# trigger_interface.net
KiCad netlist of a schematic drawn in Altium Designer
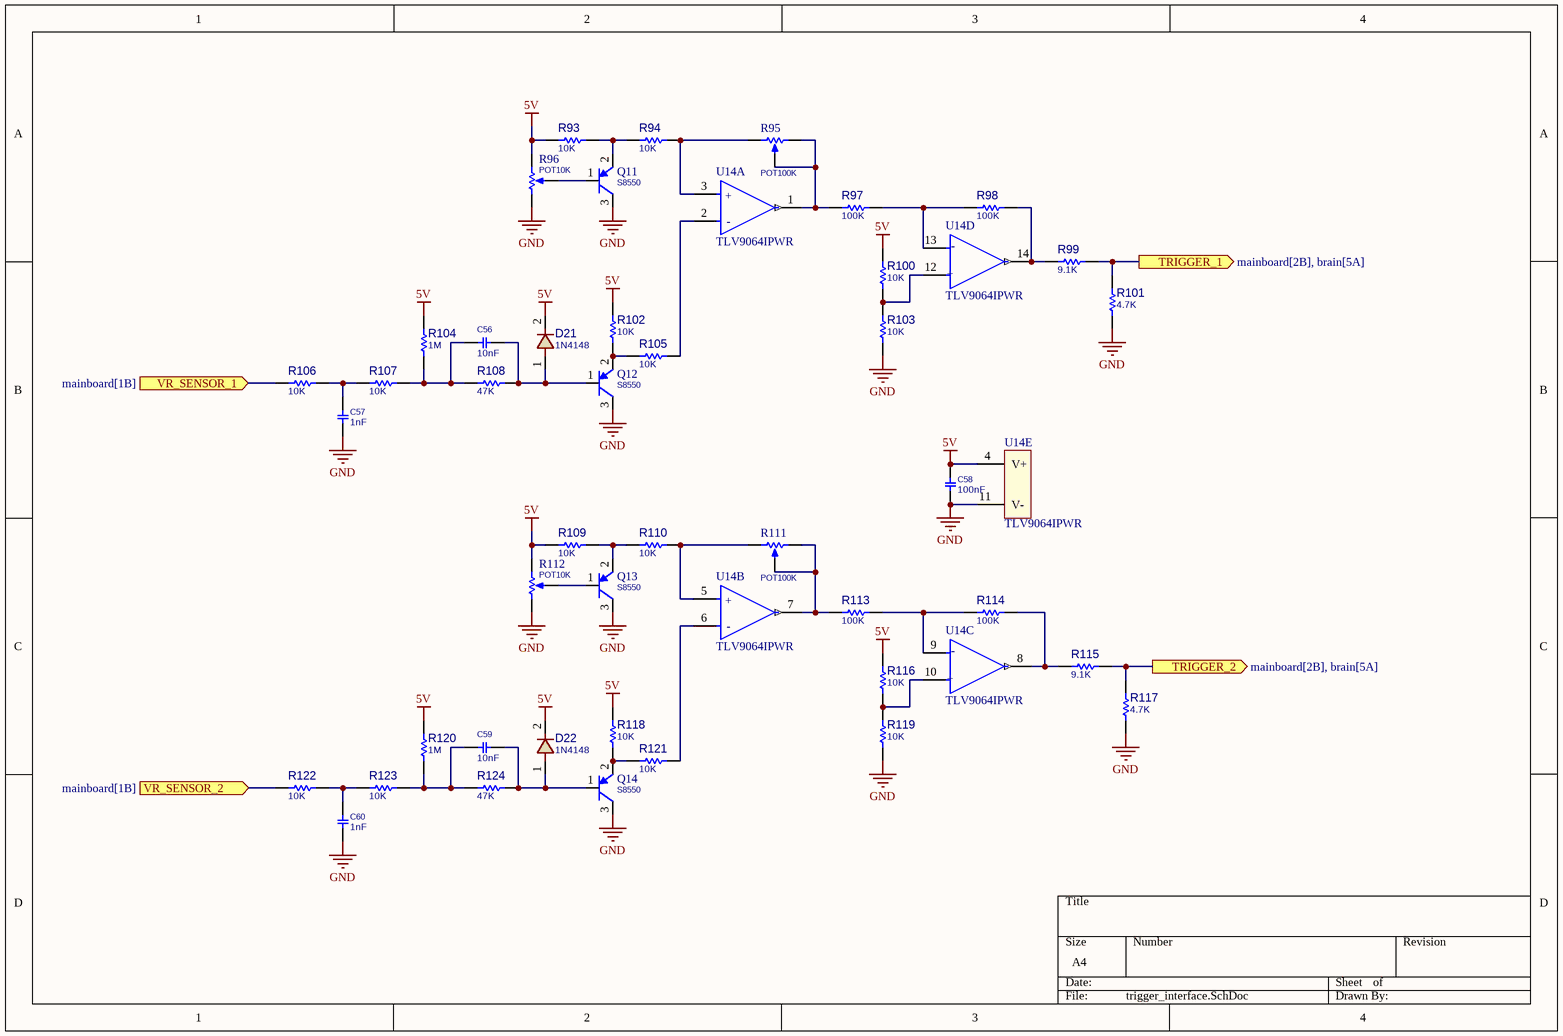
[diagram p0: trigger_interface.SchDoc]

(export (version "E")
  (design (tool "Eeschema 10.0.6"))
  (components
    (comp (ref "C56")
      (value "10nF")
      (footprint "C0805")
      (description "CAP, MLCC")
      (fields (field (name "MANF_P#") "MANF_PART#") (field (name "MANF") "Murata"))
      (libsource (lib "passive_smd") (part "CAP_SMD_MLCC"))
    )
    (comp (ref "C57")
      (value "1nF")
      (footprint "C0805")
      (description "CAP, MLCC")
      (fields (field (name "MANF_P#") "MANF_PART#") (field (name "MANF") "Murata"))
      (libsource (lib "passive_smd") (part "CAP_SMD_MLCC"))
    )
    (comp (ref "C58")
      (value "100nF")
      (footprint "C0805")
      (description "CAP, MLCC")
      (fields (field (name "MANF_P#") "MANF_PART#") (field (name "MANF") "Murata"))
      (libsource (lib "passive_smd") (part "CAP_SMD_MLCC"))
    )
    (comp (ref "C59")
      (value "10nF")
      (footprint "C0805")
      (description "CAP, MLCC")
      (fields (field (name "MANF_P#") "MANF_PART#") (field (name "MANF") "Murata"))
      (libsource (lib "passive_smd") (part "CAP_SMD_MLCC"))
    )
    (comp (ref "C60")
      (value "1nF")
      (footprint "C0805")
      (description "CAP, MLCC")
      (fields (field (name "MANF_P#") "MANF_PART#") (field (name "MANF") "Murata"))
      (libsource (lib "passive_smd") (part "CAP_SMD_MLCC"))
    )
    (comp (ref "D21")
      (value "1N4148")
      (footprint "D_SOD80")
      (description "DIODE, FAST SWTICHING, 0.3A, 0.5W")
      (fields (field (name "MANF") "MANF"))
      (libsource (lib "diode") (part "DIODE_SMD_1N4148_SOD80"))
    )
    (comp (ref "D22")
      (value "1N4148")
      (footprint "D_SOD80")
      (description "DIODE, FAST SWTICHING, 0.3A, 0.5W")
      (fields (field (name "MANF") "MANF"))
      (libsource (lib "diode") (part "DIODE_SMD_1N4148_SOD80"))
    )
    (comp (ref "Q11")
      (value "S8550")
      (footprint "SOT23_3")
      (description "BJT, PNP, 25v, 0.5A, SMD, SOT23")
      (libsource (lib "transistor_bjt") (part "PNP_S8550_SOT23"))
    )
    (comp (ref "Q12")
      (value "S8550")
      (footprint "SOT23_3")
      (description "BJT, PNP, 25v, 0.5A, SMD, SOT23")
      (libsource (lib "transistor_bjt") (part "PNP_S8550_SOT23"))
    )
    (comp (ref "Q13")
      (value "S8550")
      (footprint "SOT23_3")
      (description "BJT, PNP, 25v, 0.5A, SMD, SOT23")
      (libsource (lib "transistor_bjt") (part "PNP_S8550_SOT23"))
    )
    (comp (ref "Q14")
      (value "S8550")
      (footprint "SOT23_3")
      (description "BJT, PNP, 25v, 0.5A, SMD, SOT23")
      (libsource (lib "transistor_bjt") (part "PNP_S8550_SOT23"))
    )
    (comp (ref "R93")
      (value "10K")
      (footprint "R0805")
      (description "RESISTOR, SMD")
      (libsource (lib "passive_smd") (part "RES_SMD"))
    )
    (comp (ref "R94")
      (value "10K")
      (footprint "R0805")
      (description "RESISTOR, SMD")
      (libsource (lib "passive_smd") (part "RES_SMD"))
    )
    (comp (ref "R95")
      (value "POT100K")
      (footprint "POT_7X5")
      (description "RESISTOR, THD, Potentiometer")
      (libsource (lib "resistor_pot_trimmer") (part "RES_THD_POT_7X5"))
    )
    (comp (ref "R96")
      (value "POT10K")
      (footprint "POT_7X5")
      (description "RESISTOR, THD, Potentiometer")
      (libsource (lib "resistor_pot_trimmer") (part "RES_THD_POT_7X5"))
    )
    (comp (ref "R97")
      (value "100K")
      (footprint "R0805")
      (description "RESISTOR, SMD")
      (libsource (lib "passive_smd") (part "RES_SMD"))
    )
    (comp (ref "R98")
      (value "100K")
      (footprint "R0805")
      (description "RESISTOR, SMD")
      (libsource (lib "passive_smd") (part "RES_SMD"))
    )
    (comp (ref "R99")
      (value "9.1K")
      (footprint "R0805")
      (description "RESISTOR, SMD")
      (libsource (lib "passive_smd") (part "RES_SMD"))
    )
    (comp (ref "R100")
      (value "10K")
      (footprint "R0805")
      (description "RESISTOR, SMD")
      (libsource (lib "passive_smd") (part "RES_SMD"))
    )
    (comp (ref "R101")
      (value "4.7K")
      (footprint "R0805")
      (description "RESISTOR, SMD")
      (libsource (lib "passive_smd") (part "RES_SMD"))
    )
    (comp (ref "R102")
      (value "10K")
      (footprint "R0805")
      (description "RESISTOR, SMD")
      (libsource (lib "passive_smd") (part "RES_SMD"))
    )
    (comp (ref "R103")
      (value "10K")
      (footprint "R0805")
      (description "RESISTOR, SMD")
      (libsource (lib "passive_smd") (part "RES_SMD"))
    )
    (comp (ref "R104")
      (value "1M")
      (footprint "R0805")
      (description "RESISTOR, SMD")
      (libsource (lib "passive_smd") (part "RES_SMD"))
    )
    (comp (ref "R105")
      (value "10K")
      (footprint "R0805")
      (description "RESISTOR, SMD")
      (libsource (lib "passive_smd") (part "RES_SMD"))
    )
    (comp (ref "R106")
      (value "10K")
      (footprint "R0805")
      (description "RESISTOR, SMD")
      (libsource (lib "passive_smd") (part "RES_SMD"))
    )
    (comp (ref "R107")
      (value "10K")
      (footprint "R0805")
      (description "RESISTOR, SMD")
      (libsource (lib "passive_smd") (part "RES_SMD"))
    )
    (comp (ref "R108")
      (value "47K")
      (footprint "R0805")
      (description "RESISTOR, SMD")
      (libsource (lib "passive_smd") (part "RES_SMD"))
    )
    (comp (ref "R109")
      (value "10K")
      (footprint "R0805")
      (description "RESISTOR, SMD")
      (libsource (lib "passive_smd") (part "RES_SMD"))
    )
    (comp (ref "R110")
      (value "10K")
      (footprint "R0805")
      (description "RESISTOR, SMD")
      (libsource (lib "passive_smd") (part "RES_SMD"))
    )
    (comp (ref "R111")
      (value "POT100K")
      (footprint "POT_7X5")
      (description "RESISTOR, THD, Potentiometer")
      (libsource (lib "resistor_pot_trimmer") (part "RES_THD_POT_7X5"))
    )
    (comp (ref "R112")
      (value "POT10K")
      (footprint "POT_7X5")
      (description "RESISTOR, THD, Potentiometer")
      (libsource (lib "resistor_pot_trimmer") (part "RES_THD_POT_7X5"))
    )
    (comp (ref "R113")
      (value "100K")
      (footprint "R0805")
      (description "RESISTOR, SMD")
      (libsource (lib "passive_smd") (part "RES_SMD"))
    )
    (comp (ref "R114")
      (value "100K")
      (footprint "R0805")
      (description "RESISTOR, SMD")
      (libsource (lib "passive_smd") (part "RES_SMD"))
    )
    (comp (ref "R115")
      (value "9.1K")
      (footprint "R0805")
      (description "RESISTOR, SMD")
      (libsource (lib "passive_smd") (part "RES_SMD"))
    )
    (comp (ref "R116")
      (value "10K")
      (footprint "R0805")
      (description "RESISTOR, SMD")
      (libsource (lib "passive_smd") (part "RES_SMD"))
    )
    (comp (ref "R117")
      (value "4.7K")
      (footprint "R0805")
      (description "RESISTOR, SMD")
      (libsource (lib "passive_smd") (part "RES_SMD"))
    )
    (comp (ref "R118")
      (value "10K")
      (footprint "R0805")
      (description "RESISTOR, SMD")
      (libsource (lib "passive_smd") (part "RES_SMD"))
    )
    (comp (ref "R119")
      (value "10K")
      (footprint "R0805")
      (description "RESISTOR, SMD")
      (libsource (lib "passive_smd") (part "RES_SMD"))
    )
    (comp (ref "R120")
      (value "1M")
      (footprint "R0805")
      (description "RESISTOR, SMD")
      (libsource (lib "passive_smd") (part "RES_SMD"))
    )
    (comp (ref "R121")
      (value "10K")
      (footprint "R0805")
      (description "RESISTOR, SMD")
      (libsource (lib "passive_smd") (part "RES_SMD"))
    )
    (comp (ref "R122")
      (value "10K")
      (footprint "R0805")
      (description "RESISTOR, SMD")
      (libsource (lib "passive_smd") (part "RES_SMD"))
    )
    (comp (ref "R123")
      (value "10K")
      (footprint "R0805")
      (description "RESISTOR, SMD")
      (libsource (lib "passive_smd") (part "RES_SMD"))
    )
    (comp (ref "R124")
      (value "47K")
      (footprint "R0805")
      (description "RESISTOR, SMD")
      (libsource (lib "passive_smd") (part "RES_SMD"))
    )
    (comp (ref "U14")
      (value "TLV9064IPWR")
      (footprint "TTSOP-14")
      (description "IC CMOS 4 CIRCUIT 14TSSOP")
      (libsource (lib "") (part "TLV9064_1"))
    )
  )
  (nets
    (net (code "1") (name "/TRIGGER_1") (class "Default")
      (node (ref "R101") (pin "2") (pinfunction "2_2") (pintype "passive"))
      (node (ref "R99") (pin "2") (pinfunction "2_2") (pintype "passive"))
    )
    (net (code "2") (name "/TRIGGER_2") (class "Default")
      (node (ref "R115") (pin "2") (pinfunction "2_2") (pintype "passive"))
      (node (ref "R117") (pin "2") (pinfunction "2_2") (pintype "passive"))
    )
    (net (code "3") (name "/VR_SENSOR_1") (class "Default")
      (node (ref "R106") (pin "2") (pinfunction "2_2") (pintype "passive"))
    )
    (net (code "4") (name "/VR_SENSOR_2") (class "Default")
      (node (ref "R122") (pin "2") (pinfunction "2_2") (pintype "passive"))
    )
    (net (code "5") (name "5V") (class "Default")
      (node (ref "C58") (pin "2") (pinfunction "2_2") (pintype "passive"))
      (node (ref "D21") (pin "2") (pinfunction "2_2") (pintype "passive"))
      (node (ref "D22") (pin "2") (pinfunction "2_2") (pintype "passive"))
      (node (ref "R100") (pin "2") (pinfunction "2_2") (pintype "passive"))
      (node (ref "R102") (pin "1") (pinfunction "1_1") (pintype "passive"))
      (node (ref "R104") (pin "1") (pinfunction "1_1") (pintype "passive"))
      (node (ref "R109") (pin "1") (pinfunction "1_1") (pintype "passive"))
      (node (ref "R112") (pin "3") (pinfunction "BOT_3") (pintype "passive"))
      (node (ref "R116") (pin "2") (pinfunction "2_2") (pintype "passive"))
      (node (ref "R118") (pin "1") (pinfunction "1_1") (pintype "passive"))
      (node (ref "R120") (pin "1") (pinfunction "1_1") (pintype "passive"))
      (node (ref "R93") (pin "1") (pinfunction "1_1") (pintype "passive"))
      (node (ref "R96") (pin "3") (pinfunction "BOT_3") (pintype "passive"))
      (node (ref "U14") (pin "4") (pinfunction "V+_4") (pintype "power_in"))
    )
    (net (code "6") (name "GND") (class "Default")
      (node (ref "C57") (pin "1") (pinfunction "1_1") (pintype "passive"))
      (node (ref "C58") (pin "1") (pinfunction "1_1") (pintype "passive"))
      (node (ref "C60") (pin "1") (pinfunction "1_1") (pintype "passive"))
      (node (ref "Q11") (pin "3") (pinfunction "C_3") (pintype "passive"))
      (node (ref "Q12") (pin "3") (pinfunction "C_3") (pintype "passive"))
      (node (ref "Q13") (pin "3") (pinfunction "C_3") (pintype "passive"))
      (node (ref "Q14") (pin "3") (pinfunction "C_3") (pintype "passive"))
      (node (ref "R101") (pin "1") (pinfunction "1_1") (pintype "passive"))
      (node (ref "R103") (pin "2") (pinfunction "2_2") (pintype "passive"))
      (node (ref "R112") (pin "1") (pinfunction "TOP_1") (pintype "passive"))
      (node (ref "R117") (pin "1") (pinfunction "1_1") (pintype "passive"))
      (node (ref "R119") (pin "2") (pinfunction "2_2") (pintype "passive"))
      (node (ref "R96") (pin "1") (pinfunction "TOP_1") (pintype "passive"))
      (node (ref "U14") (pin "11") (pinfunction "V-_11") (pintype "power_in"))
    )
    (net (code "7") (name "Net-(C56-Pad2)") (class "Default")
      (node (ref "C56") (pin "2") (pinfunction "2_2") (pintype "passive"))
      (node (ref "R104") (pin "2") (pinfunction "2_2") (pintype "passive"))
      (node (ref "R107") (pin "1") (pinfunction "1_1") (pintype "passive"))
      (node (ref "R108") (pin "2") (pinfunction "2_2") (pintype "passive"))
    )
    (net (code "8") (name "Net-(C57-Pad2)") (class "Default")
      (node (ref "C57") (pin "2") (pinfunction "2_2") (pintype "passive"))
      (node (ref "R106") (pin "1") (pinfunction "1_1") (pintype "passive"))
      (node (ref "R107") (pin "2") (pinfunction "2_2") (pintype "passive"))
    )
    (net (code "9") (name "Net-(C59-Pad2)") (class "Default")
      (node (ref "C59") (pin "2") (pinfunction "2_2") (pintype "passive"))
      (node (ref "R120") (pin "2") (pinfunction "2_2") (pintype "passive"))
      (node (ref "R123") (pin "1") (pinfunction "1_1") (pintype "passive"))
      (node (ref "R124") (pin "2") (pinfunction "2_2") (pintype "passive"))
    )
    (net (code "10") (name "Net-(C60-Pad2)") (class "Default")
      (node (ref "C60") (pin "2") (pinfunction "2_2") (pintype "passive"))
      (node (ref "R122") (pin "1") (pinfunction "1_1") (pintype "passive"))
      (node (ref "R123") (pin "2") (pinfunction "2_2") (pintype "passive"))
    )
    (net (code "11") (name "Net-(Q11-B)") (class "Default")
      (node (ref "Q11") (pin "1") (pinfunction "B_1") (pintype "passive"))
      (node (ref "R96") (pin "2") (pinfunction "TAP_2") (pintype "passive"))
    )
    (net (code "12") (name "Net-(Q11-E)") (class "Default")
      (node (ref "Q11") (pin "2") (pinfunction "E_2") (pintype "passive"))
      (node (ref "R93") (pin "2") (pinfunction "2_2") (pintype "passive"))
      (node (ref "R94") (pin "1") (pinfunction "1_1") (pintype "passive"))
    )
    (net (code "13") (name "Net-(Q12-B)") (class "Default")
      (node (ref "C56") (pin "1") (pinfunction "1_1") (pintype "passive"))
      (node (ref "D21") (pin "1") (pinfunction "1_1") (pintype "passive"))
      (node (ref "Q12") (pin "1") (pinfunction "B_1") (pintype "passive"))
      (node (ref "R108") (pin "1") (pinfunction "1_1") (pintype "passive"))
    )
    (net (code "14") (name "Net-(Q12-E)") (class "Default")
      (node (ref "Q12") (pin "2") (pinfunction "E_2") (pintype "passive"))
      (node (ref "R102") (pin "2") (pinfunction "2_2") (pintype "passive"))
      (node (ref "R105") (pin "1") (pinfunction "1_1") (pintype "passive"))
    )
    (net (code "15") (name "Net-(Q13-B)") (class "Default")
      (node (ref "Q13") (pin "1") (pinfunction "B_1") (pintype "passive"))
      (node (ref "R112") (pin "2") (pinfunction "TAP_2") (pintype "passive"))
    )
    (net (code "16") (name "Net-(Q13-E)") (class "Default")
      (node (ref "Q13") (pin "2") (pinfunction "E_2") (pintype "passive"))
      (node (ref "R109") (pin "2") (pinfunction "2_2") (pintype "passive"))
      (node (ref "R110") (pin "1") (pinfunction "1_1") (pintype "passive"))
    )
    (net (code "17") (name "Net-(Q14-B)") (class "Default")
      (node (ref "C59") (pin "1") (pinfunction "1_1") (pintype "passive"))
      (node (ref "D22") (pin "1") (pinfunction "1_1") (pintype "passive"))
      (node (ref "Q14") (pin "1") (pinfunction "B_1") (pintype "passive"))
      (node (ref "R124") (pin "1") (pinfunction "1_1") (pintype "passive"))
    )
    (net (code "18") (name "Net-(Q14-E)") (class "Default")
      (node (ref "Q14") (pin "2") (pinfunction "E_2") (pintype "passive"))
      (node (ref "R118") (pin "2") (pinfunction "2_2") (pintype "passive"))
      (node (ref "R121") (pin "1") (pinfunction "1_1") (pintype "passive"))
    )
    (net (code "19") (name "Net-(R95-BOT)") (class "Default")
      (node (ref "R95") (pin "2") (pinfunction "TAP_2") (pintype "passive"))
      (node (ref "R95") (pin "3") (pinfunction "BOT_3") (pintype "passive"))
      (node (ref "R97") (pin "1") (pinfunction "1_1") (pintype "passive"))
      (node (ref "U14") (pin "1") (pinfunction "OUT1_1") (pintype "output"))
    )
    (net (code "20") (name "Net-(R95-TOP)") (class "Default")
      (node (ref "R94") (pin "2") (pinfunction "2_2") (pintype "passive"))
      (node (ref "R95") (pin "1") (pinfunction "TOP_1") (pintype "passive"))
      (node (ref "U14") (pin "3") (pinfunction "IN1+_3") (pintype "tri_state"))
    )
    (net (code "21") (name "Net-(R111-BOT)") (class "Default")
      (node (ref "R111") (pin "2") (pinfunction "TAP_2") (pintype "passive"))
      (node (ref "R111") (pin "3") (pinfunction "BOT_3") (pintype "passive"))
      (node (ref "R113") (pin "1") (pinfunction "1_1") (pintype "passive"))
      (node (ref "U14") (pin "7") (pinfunction "OUT2_7") (pintype "output"))
    )
    (net (code "22") (name "Net-(R111-TOP)") (class "Default")
      (node (ref "R110") (pin "2") (pinfunction "2_2") (pintype "passive"))
      (node (ref "R111") (pin "1") (pinfunction "TOP_1") (pintype "passive"))
      (node (ref "U14") (pin "5") (pinfunction "IN2+_5") (pintype "tri_state"))
    )
    (net (code "23") (name "Net-(U14A-IN1-)") (class "Default")
      (node (ref "R105") (pin "2") (pinfunction "2_2") (pintype "passive"))
      (node (ref "U14") (pin "2") (pinfunction "IN1-_2") (pintype "tri_state"))
    )
    (net (code "24") (name "Net-(U14B-IN2-)") (class "Default")
      (node (ref "R121") (pin "2") (pinfunction "2_2") (pintype "passive"))
      (node (ref "U14") (pin "6") (pinfunction "IN2-_6") (pintype "tri_state"))
    )
    (net (code "25") (name "Net-(U14C-IN3+)") (class "Default")
      (node (ref "R116") (pin "1") (pinfunction "1_1") (pintype "passive"))
      (node (ref "R119") (pin "1") (pinfunction "1_1") (pintype "passive"))
      (node (ref "U14") (pin "10") (pinfunction "IN3+_10") (pintype "tri_state"))
    )
    (net (code "26") (name "Net-(U14C-IN3-)") (class "Default")
      (node (ref "R113") (pin "2") (pinfunction "2_2") (pintype "passive"))
      (node (ref "R114") (pin "1") (pinfunction "1_1") (pintype "passive"))
      (node (ref "U14") (pin "9") (pinfunction "IN3-_9") (pintype "tri_state"))
    )
    (net (code "27") (name "Net-(U14C-OUT3)") (class "Default")
      (node (ref "R114") (pin "2") (pinfunction "2_2") (pintype "passive"))
      (node (ref "R115") (pin "1") (pinfunction "1_1") (pintype "passive"))
      (node (ref "U14") (pin "8") (pinfunction "OUT3_8") (pintype "output"))
    )
    (net (code "28") (name "Net-(U14D-IN4+)") (class "Default")
      (node (ref "R100") (pin "1") (pinfunction "1_1") (pintype "passive"))
      (node (ref "R103") (pin "1") (pinfunction "1_1") (pintype "passive"))
      (node (ref "U14") (pin "12") (pinfunction "IN4+_12") (pintype "tri_state"))
    )
    (net (code "29") (name "Net-(U14D-IN4-)") (class "Default")
      (node (ref "R97") (pin "2") (pinfunction "2_2") (pintype "passive"))
      (node (ref "R98") (pin "1") (pinfunction "1_1") (pintype "passive"))
      (node (ref "U14") (pin "13") (pinfunction "IN4-_13") (pintype "tri_state"))
    )
    (net (code "30") (name "Net-(U14D-OUT4)") (class "Default")
      (node (ref "R98") (pin "2") (pinfunction "2_2") (pintype "passive"))
      (node (ref "R99") (pin "1") (pinfunction "1_1") (pintype "passive"))
      (node (ref "U14") (pin "14") (pinfunction "OUT4_14") (pintype "output"))
    )
  )
)
